# MicrocontrollerPorts.net
KiCad netlist of a schematic drawn in Altium Designer
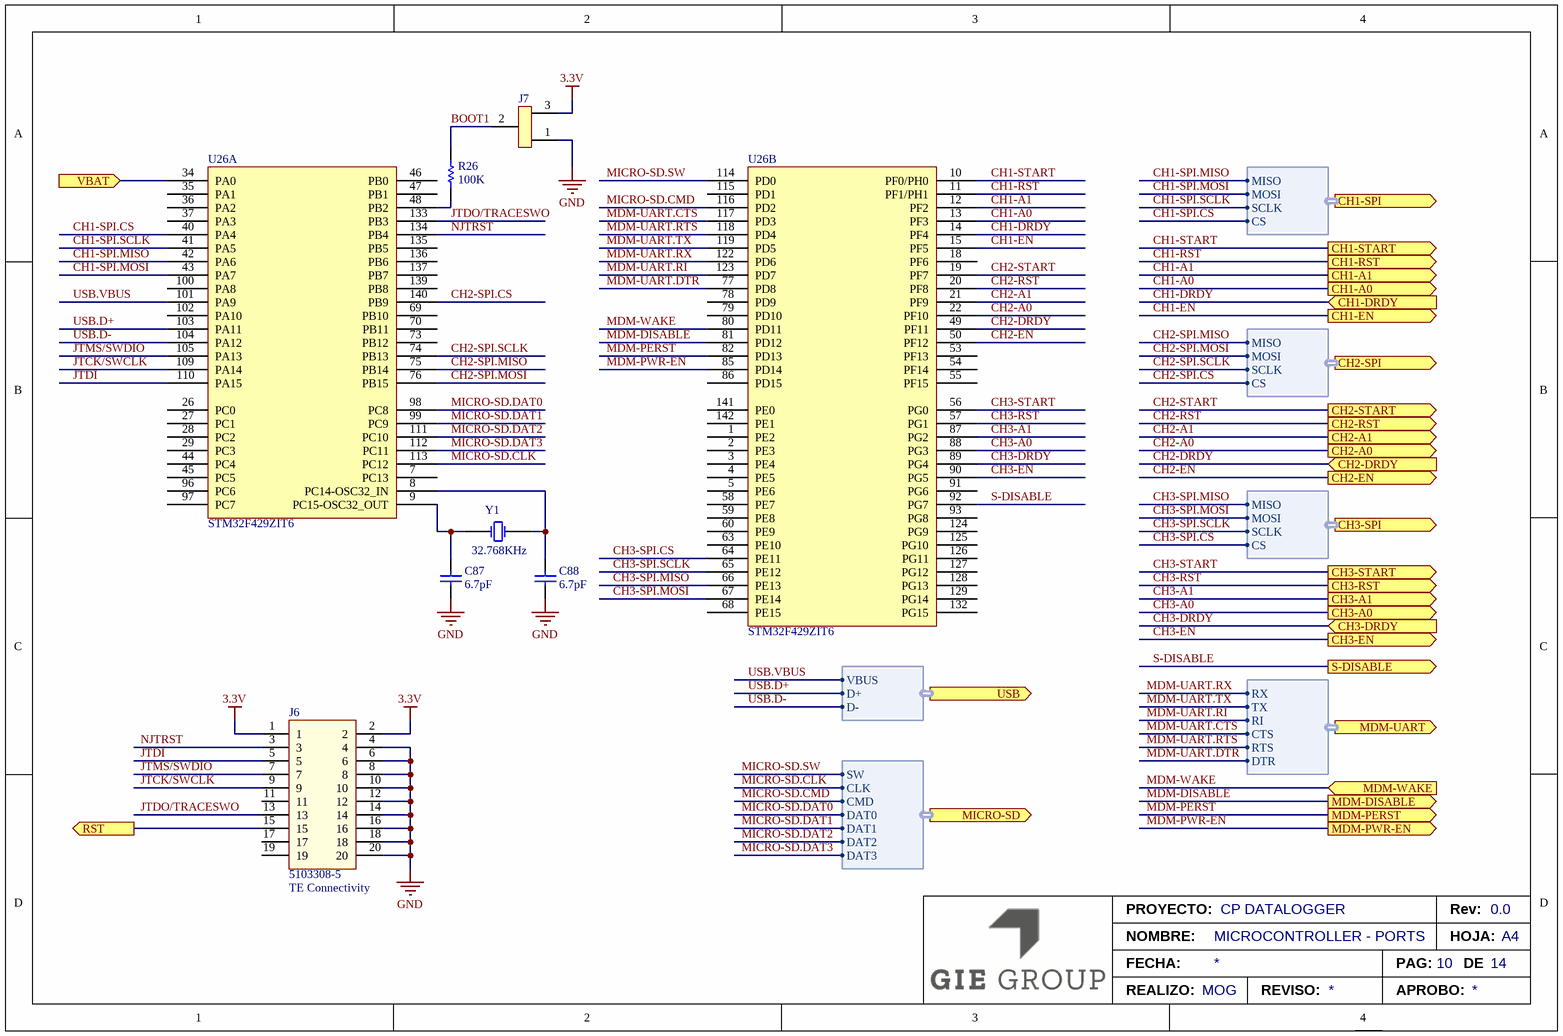
[diagram p0: MicrocontrollerPorts.SchDoc]

(export (version "E")
  (design (tool "Eeschema 10.0.6"))
  (components
    (comp (ref "C87")
      (value "6.7pF")
      (footprint "CAP-0603")
      (description "CAP CER 6.7 pF 50V C0G 0603")
      (fields (field (name "PARTNUMBER") "CBR06C679B5GAC") (field (name "MANUFACTURER") "Kemet"))
      (libsource (lib "Kemet") (part "CBR06C679B5GAC"))
    )
    (comp (ref "C88")
      (value "6.7pF")
      (footprint "CAP-0603")
      (description "CAP CER 6.7 pF 50V C0G 0603")
      (fields (field (name "PARTNUMBER") "CBR06C679B5GAC") (field (name "MANUFACTURER") "Kemet"))
      (libsource (lib "Kemet") (part "CBR06C679B5GAC"))
    )
    (comp (ref "J6")
      (value "5103308-5")
      (footprint "TE-5103308-5")
      (description "CONN HEADER VERT 20POS 2.54MM")
      (fields (field (name "PARTNUMBER") "5103308-5") (field (name "MANUFACTURER") "TE Connectivity"))
      (libsource (lib "TeConnectivity") (part "5103308-5"))
    )
    (comp (ref "J7")
      (value "PRPC003SAAN-RC")
      (footprint "PIN3")
      (description "CONN HEADER .100\" SNGL STR 3POS")
      (fields (field (name "MANUFACTURER") "Sullins Connector Solutions"))
      (libsource (lib "Sullins") (part "PRPC003SAAN-RC"))
    )
    (comp (ref "R26")
      (value "100K")
      (footprint "RES-0603")
      (description "RES SMD 100K OHM 1% 1/10W 0603")
      (fields (field (name "TOLERANCE") "1%") (field (name "MANUFACTURER") "Yageo"))
      (libsource (lib "Yageo") (part "RC0603FR-07100KL"))
    )
    (comp (ref "U26")
      (value "STM32F429ZIT6")
      (footprint "LQFP144")
      (description "IC MCU 32BIT 2MB FLASH 144LQFP")
      (fields (field (name "MANUFACTURER") "STMicroelectronics"))
      (libsource (lib "STMicroelectronics") (part "STM32F429ZIT6"))
    )
    (comp (ref "Y1")
      (value "32.768KHz")
      (footprint "XTAL-ABS07")
      (description "CRYSTAL 32.768KHZ 7PF SMD")
      (fields (field (name "PARTNUMBER") "ABS07-32.768KHZ-7-T") (field (name "MANUFACTURER") "Abracon"))
      (libsource (lib "Abracon") (part "ABS07-32.768KHZ-7-T"))
    )
  )
  (nets
    (net (code "7") (name "/BOOT1") (class "Default")
      (node (ref "J7") (pin "2") (pinfunction "2_2") (pintype "passive"))
      (node (ref "R26") (pin "2") (pinfunction "2_2") (pintype "passive"))
    )
    (net (code "8") (name "/CH1-A0") (class "Default")
      (node (ref "U26") (pin "13") (pinfunction "PF3_13") (pintype "passive"))
    )
    (net (code "9") (name "/CH1-A1") (class "Default")
      (node (ref "U26") (pin "12") (pinfunction "PF2_12") (pintype "passive"))
    )
    (net (code "10") (name "/CH1-DRDY") (class "Default")
      (node (ref "U26") (pin "14") (pinfunction "PF4_14") (pintype "passive"))
    )
    (net (code "11") (name "/CH1-EN") (class "Default")
      (node (ref "U26") (pin "15") (pinfunction "PF5_15") (pintype "passive"))
    )
    (net (code "12") (name "/CH1-RST") (class "Default")
      (node (ref "U26") (pin "11") (pinfunction "PF1/PH1_11") (pintype "passive"))
    )
    (net (code "13") (name "/CH1-SPI.CS") (class "Default")
      (node (ref "U26") (pin "40") (pinfunction "PA4_40") (pintype "passive"))
    )
    (net (code "14") (name "/CH1-SPI.MISO") (class "Default")
      (node (ref "U26") (pin "42") (pinfunction "PA6_42") (pintype "passive"))
    )
    (net (code "15") (name "/CH1-SPI.MOSI") (class "Default")
      (node (ref "U26") (pin "43") (pinfunction "PA7_43") (pintype "passive"))
    )
    (net (code "16") (name "/CH1-SPI.SCLK") (class "Default")
      (node (ref "U26") (pin "41") (pinfunction "PA5_41") (pintype "passive"))
    )
    (net (code "17") (name "/CH1-START") (class "Default")
      (node (ref "U26") (pin "10") (pinfunction "PF0/PH0_10") (pintype "passive"))
    )
    (net (code "18") (name "/CH2-A0") (class "Default")
      (node (ref "U26") (pin "22") (pinfunction "PF10_22") (pintype "passive"))
    )
    (net (code "19") (name "/CH2-A1") (class "Default")
      (node (ref "U26") (pin "21") (pinfunction "PF9_21") (pintype "passive"))
    )
    (net (code "20") (name "/CH2-DRDY") (class "Default")
      (node (ref "U26") (pin "49") (pinfunction "PF11_49") (pintype "passive"))
    )
    (net (code "21") (name "/CH2-EN") (class "Default")
      (node (ref "U26") (pin "50") (pinfunction "PF12_50") (pintype "passive"))
    )
    (net (code "22") (name "/CH2-RST") (class "Default")
      (node (ref "U26") (pin "20") (pinfunction "PF8_20") (pintype "passive"))
    )
    (net (code "23") (name "/CH2-SPI.CS") (class "Default")
      (node (ref "U26") (pin "140") (pinfunction "PB9_140") (pintype "passive"))
    )
    (net (code "24") (name "/CH2-SPI.MISO") (class "Default")
      (node (ref "U26") (pin "75") (pinfunction "PB14_75") (pintype "passive"))
    )
    (net (code "25") (name "/CH2-SPI.MOSI") (class "Default")
      (node (ref "U26") (pin "76") (pinfunction "PB15_76") (pintype "passive"))
    )
    (net (code "26") (name "/CH2-SPI.SCLK") (class "Default")
      (node (ref "U26") (pin "74") (pinfunction "PB13_74") (pintype "passive"))
    )
    (net (code "27") (name "/CH2-START") (class "Default")
      (node (ref "U26") (pin "19") (pinfunction "PF7_19") (pintype "passive"))
    )
    (net (code "28") (name "/CH3-A0") (class "Default")
      (node (ref "U26") (pin "88") (pinfunction "PG3_88") (pintype "passive"))
    )
    (net (code "29") (name "/CH3-A1") (class "Default")
      (node (ref "U26") (pin "87") (pinfunction "PG2_87") (pintype "passive"))
    )
    (net (code "30") (name "/CH3-DRDY") (class "Default")
      (node (ref "U26") (pin "89") (pinfunction "PG4_89") (pintype "passive"))
    )
    (net (code "31") (name "/CH3-EN") (class "Default")
      (node (ref "U26") (pin "90") (pinfunction "PG5_90") (pintype "passive"))
    )
    (net (code "32") (name "/CH3-RST") (class "Default")
      (node (ref "U26") (pin "57") (pinfunction "PG1_57") (pintype "passive"))
    )
    (net (code "33") (name "/CH3-SPI.CS") (class "Default")
      (node (ref "U26") (pin "64") (pinfunction "PE11_64") (pintype "passive"))
    )
    (net (code "34") (name "/CH3-SPI.MISO") (class "Default")
      (node (ref "U26") (pin "66") (pinfunction "PE13_66") (pintype "passive"))
    )
    (net (code "35") (name "/CH3-SPI.MOSI") (class "Default")
      (node (ref "U26") (pin "67") (pinfunction "PE14_67") (pintype "passive"))
    )
    (net (code "36") (name "/CH3-SPI.SCLK") (class "Default")
      (node (ref "U26") (pin "65") (pinfunction "PE12_65") (pintype "passive"))
    )
    (net (code "37") (name "/CH3-START") (class "Default")
      (node (ref "U26") (pin "56") (pinfunction "PG0_56") (pintype "passive"))
    )
    (net (code "38") (name "/JTCK{slash}SWCLK") (class "Default")
      (node (ref "J6") (pin "9") (pinfunction "9_9") (pintype "passive"))
      (node (ref "U26") (pin "109") (pinfunction "PA14_109") (pintype "passive"))
    )
    (net (code "39") (name "/JTDI") (class "Default")
      (node (ref "J6") (pin "5") (pinfunction "5_5") (pintype "passive"))
      (node (ref "U26") (pin "110") (pinfunction "PA15_110") (pintype "passive"))
    )
    (net (code "40") (name "/JTDO{slash}TRACESWO") (class "Default")
      (node (ref "J6") (pin "13") (pinfunction "13_13") (pintype "passive"))
      (node (ref "U26") (pin "133") (pinfunction "PB3_133") (pintype "passive"))
    )
    (net (code "41") (name "/JTMS{slash}SWDIO") (class "Default")
      (node (ref "J6") (pin "7") (pinfunction "7_7") (pintype "passive"))
      (node (ref "U26") (pin "105") (pinfunction "PA13_105") (pintype "passive"))
    )
    (net (code "42") (name "/MDM-DISABLE") (class "Default")
      (node (ref "U26") (pin "81") (pinfunction "PD12_81") (pintype "passive"))
    )
    (net (code "43") (name "/MDM-PERST") (class "Default")
      (node (ref "U26") (pin "82") (pinfunction "PD13_82") (pintype "passive"))
    )
    (net (code "44") (name "/MDM-PWR-EN") (class "Default")
      (node (ref "U26") (pin "85") (pinfunction "PD14_85") (pintype "passive"))
    )
    (net (code "45") (name "/MDM-UART.CTS") (class "Default")
      (node (ref "U26") (pin "117") (pinfunction "PD3_117") (pintype "passive"))
    )
    (net (code "46") (name "/MDM-UART.DTR") (class "Default")
      (node (ref "U26") (pin "77") (pinfunction "PD8_77") (pintype "passive"))
    )
    (net (code "47") (name "/MDM-UART.RI") (class "Default")
      (node (ref "U26") (pin "123") (pinfunction "PD7_123") (pintype "passive"))
    )
    (net (code "48") (name "/MDM-UART.RTS") (class "Default")
      (node (ref "U26") (pin "118") (pinfunction "PD4_118") (pintype "passive"))
    )
    (net (code "49") (name "/MDM-UART.RX") (class "Default")
      (node (ref "U26") (pin "122") (pinfunction "PD6_122") (pintype "passive"))
    )
    (net (code "50") (name "/MDM-UART.TX") (class "Default")
      (node (ref "U26") (pin "119") (pinfunction "PD5_119") (pintype "passive"))
    )
    (net (code "51") (name "/MDM-WAKE") (class "Default")
      (node (ref "U26") (pin "80") (pinfunction "PD11_80") (pintype "passive"))
    )
    (net (code "52") (name "/MICRO-SD.CLK") (class "Default")
      (node (ref "U26") (pin "113") (pinfunction "PC12_113") (pintype "passive"))
    )
    (net (code "53") (name "/MICRO-SD.CMD") (class "Default")
      (node (ref "U26") (pin "116") (pinfunction "PD2_116") (pintype "passive"))
    )
    (net (code "54") (name "/MICRO-SD.DAT0") (class "Default")
      (node (ref "U26") (pin "98") (pinfunction "PC8_98") (pintype "passive"))
    )
    (net (code "55") (name "/MICRO-SD.DAT1") (class "Default")
      (node (ref "U26") (pin "99") (pinfunction "PC9_99") (pintype "passive"))
    )
    (net (code "56") (name "/MICRO-SD.DAT2") (class "Default")
      (node (ref "U26") (pin "111") (pinfunction "PC10_111") (pintype "passive"))
    )
    (net (code "57") (name "/MICRO-SD.DAT3") (class "Default")
      (node (ref "U26") (pin "112") (pinfunction "PC11_112") (pintype "passive"))
    )
    (net (code "58") (name "/MICRO-SD.SW") (class "Default")
      (node (ref "U26") (pin "114") (pinfunction "PD0_114") (pintype "passive"))
    )
    (net (code "59") (name "/NJTRST") (class "Default")
      (node (ref "J6") (pin "3") (pinfunction "3_3") (pintype "passive"))
      (node (ref "U26") (pin "134") (pinfunction "PB4_134") (pintype "passive"))
    )
    (net (code "60") (name "/RST") (class "Default")
      (node (ref "J6") (pin "15") (pinfunction "15_15") (pintype "passive"))
    )
    (net (code "61") (name "/S-DISABLE") (class "Default")
      (node (ref "U26") (pin "92") (pinfunction "PG7_92") (pintype "passive"))
    )
    (net (code "62") (name "/USB.D+") (class "Default")
      (node (ref "U26") (pin "103") (pinfunction "PA11_103") (pintype "passive"))
    )
    (net (code "63") (name "/USB.D-") (class "Default")
      (node (ref "U26") (pin "104") (pinfunction "PA12_104") (pintype "passive"))
    )
    (net (code "64") (name "/USB.VBUS") (class "Default")
      (node (ref "U26") (pin "101") (pinfunction "PA9_101") (pintype "passive"))
    )
    (net (code "65") (name "/VBAT") (class "Default")
      (node (ref "U26") (pin "34") (pinfunction "PA0_34") (pintype "passive"))
    )
    (net (code "72") (name "3.3V") (class "Default")
      (node (ref "J6") (pin "1") (pinfunction "1_1") (pintype "passive"))
      (node (ref "J6") (pin "2") (pinfunction "2_2") (pintype "passive"))
      (node (ref "J7") (pin "3") (pinfunction "3_3") (pintype "passive"))
    )
    (net (code "73") (name "GND") (class "Default")
      (node (ref "C87") (pin "1") (pinfunction "1_1") (pintype "passive"))
      (node (ref "C88") (pin "1") (pinfunction "1_1") (pintype "passive"))
      (node (ref "J6") (pin "10") (pinfunction "10_10") (pintype "passive"))
      (node (ref "J6") (pin "12") (pinfunction "12_12") (pintype "passive"))
      (node (ref "J6") (pin "14") (pinfunction "14_14") (pintype "passive"))
      (node (ref "J6") (pin "16") (pinfunction "16_16") (pintype "passive"))
      (node (ref "J6") (pin "18") (pinfunction "18_18") (pintype "passive"))
      (node (ref "J6") (pin "20") (pinfunction "20_20") (pintype "passive"))
      (node (ref "J6") (pin "4") (pinfunction "4_4") (pintype "passive"))
      (node (ref "J6") (pin "6") (pinfunction "6_6") (pintype "passive"))
      (node (ref "J6") (pin "8") (pinfunction "8_8") (pintype "passive"))
      (node (ref "J7") (pin "1") (pinfunction "1_1") (pintype "passive"))
    )
    (net (code "74") (name "Net-(U26A-PB2)") (class "Default")
      (node (ref "R26") (pin "1") (pinfunction "1_1") (pintype "passive"))
      (node (ref "U26") (pin "48") (pinfunction "PB2_48") (pintype "passive"))
    )
    (net (code "75") (name "Net-(U26A-PC14-OSC32_IN)") (class "Default")
      (node (ref "C88") (pin "2") (pinfunction "2_2") (pintype "passive"))
      (node (ref "U26") (pin "8") (pinfunction "PC14-OSC32_IN_8") (pintype "passive"))
      (node (ref "Y1") (pin "1") (pinfunction "OSC1_1") (pintype "passive"))
    )
    (net (code "76") (name "Net-(U26A-PC15-OSC32_OUT)") (class "Default")
      (node (ref "C87") (pin "2") (pinfunction "2_2") (pintype "passive"))
      (node (ref "U26") (pin "9") (pinfunction "PC15-OSC32_OUT_9") (pintype "passive"))
      (node (ref "Y1") (pin "2") (pinfunction "OSC2_2") (pintype "passive"))
    )
    (net (code "77") (name "unconnected-(J6-Pad11)") (class "Default")
      (node (ref "J6") (pin "11") (pinfunction "11_11") (pintype "passive"))
    )
    (net (code "78") (name "unconnected-(J6-Pad17)") (class "Default")
      (node (ref "J6") (pin "17") (pinfunction "17_17") (pintype "passive"))
    )
    (net (code "79") (name "unconnected-(J6-Pad19)") (class "Default")
      (node (ref "J6") (pin "19") (pinfunction "19_19") (pintype "passive"))
    )
    (net (code "80") (name "unconnected-(U26A-PA1-Pad35)") (class "Default")
      (node (ref "U26") (pin "35") (pinfunction "PA1_35") (pintype "passive"))
    )
    (net (code "81") (name "unconnected-(U26A-PA2-Pad36)") (class "Default")
      (node (ref "U26") (pin "36") (pinfunction "PA2_36") (pintype "passive"))
    )
    (net (code "82") (name "unconnected-(U26A-PA3-Pad37)") (class "Default")
      (node (ref "U26") (pin "37") (pinfunction "PA3_37") (pintype "passive"))
    )
    (net (code "83") (name "unconnected-(U26A-PA8-Pad100)") (class "Default")
      (node (ref "U26") (pin "100") (pinfunction "PA8_100") (pintype "passive"))
    )
    (net (code "84") (name "unconnected-(U26A-PA10-Pad102)") (class "Default")
      (node (ref "U26") (pin "102") (pinfunction "PA10_102") (pintype "passive"))
    )
    (net (code "85") (name "unconnected-(U26A-PB0-Pad46)") (class "Default")
      (node (ref "U26") (pin "46") (pinfunction "PB0_46") (pintype "passive"))
    )
    (net (code "86") (name "unconnected-(U26A-PB1-Pad47)") (class "Default")
      (node (ref "U26") (pin "47") (pinfunction "PB1_47") (pintype "passive"))
    )
    (net (code "87") (name "unconnected-(U26A-PB5-Pad135)") (class "Default")
      (node (ref "U26") (pin "135") (pinfunction "PB5_135") (pintype "passive"))
    )
    (net (code "88") (name "unconnected-(U26A-PB6-Pad136)") (class "Default")
      (node (ref "U26") (pin "136") (pinfunction "PB6_136") (pintype "passive"))
    )
    (net (code "89") (name "unconnected-(U26A-PB7-Pad137)") (class "Default")
      (node (ref "U26") (pin "137") (pinfunction "PB7_137") (pintype "passive"))
    )
    (net (code "90") (name "unconnected-(U26A-PB8-Pad139)") (class "Default")
      (node (ref "U26") (pin "139") (pinfunction "PB8_139") (pintype "passive"))
    )
    (net (code "91") (name "unconnected-(U26A-PB10-Pad69)") (class "Default")
      (node (ref "U26") (pin "69") (pinfunction "PB10_69") (pintype "passive"))
    )
    (net (code "92") (name "unconnected-(U26A-PB11-Pad70)") (class "Default")
      (node (ref "U26") (pin "70") (pinfunction "PB11_70") (pintype "passive"))
    )
    (net (code "93") (name "unconnected-(U26A-PB12-Pad73)") (class "Default")
      (node (ref "U26") (pin "73") (pinfunction "PB12_73") (pintype "passive"))
    )
    (net (code "94") (name "unconnected-(U26A-PC0-Pad26)") (class "Default")
      (node (ref "U26") (pin "26") (pinfunction "PC0_26") (pintype "passive"))
    )
    (net (code "95") (name "unconnected-(U26A-PC1-Pad27)") (class "Default")
      (node (ref "U26") (pin "27") (pinfunction "PC1_27") (pintype "passive"))
    )
    (net (code "96") (name "unconnected-(U26A-PC2-Pad28)") (class "Default")
      (node (ref "U26") (pin "28") (pinfunction "PC2_28") (pintype "passive"))
    )
    (net (code "97") (name "unconnected-(U26A-PC3-Pad29)") (class "Default")
      (node (ref "U26") (pin "29") (pinfunction "PC3_29") (pintype "passive"))
    )
    (net (code "98") (name "unconnected-(U26A-PC4-Pad44)") (class "Default")
      (node (ref "U26") (pin "44") (pinfunction "PC4_44") (pintype "passive"))
    )
    (net (code "99") (name "unconnected-(U26A-PC5-Pad45)") (class "Default")
      (node (ref "U26") (pin "45") (pinfunction "PC5_45") (pintype "passive"))
    )
    (net (code "100") (name "unconnected-(U26A-PC6-Pad96)") (class "Default")
      (node (ref "U26") (pin "96") (pinfunction "PC6_96") (pintype "passive"))
    )
    (net (code "101") (name "unconnected-(U26A-PC7-Pad97)") (class "Default")
      (node (ref "U26") (pin "97") (pinfunction "PC7_97") (pintype "passive"))
    )
    (net (code "102") (name "unconnected-(U26A-PC13-Pad7)") (class "Default")
      (node (ref "U26") (pin "7") (pinfunction "PC13_7") (pintype "passive"))
    )
    (net (code "103") (name "unconnected-(U26B-PD1-Pad115)") (class "Default")
      (node (ref "U26") (pin "115") (pinfunction "PD1_115") (pintype "passive"))
    )
    (net (code "104") (name "unconnected-(U26B-PD9-Pad78)") (class "Default")
      (node (ref "U26") (pin "78") (pinfunction "PD9_78") (pintype "passive"))
    )
    (net (code "105") (name "unconnected-(U26B-PD10-Pad79)") (class "Default")
      (node (ref "U26") (pin "79") (pinfunction "PD10_79") (pintype "passive"))
    )
    (net (code "106") (name "unconnected-(U26B-PD15-Pad86)") (class "Default")
      (node (ref "U26") (pin "86") (pinfunction "PD15_86") (pintype "passive"))
    )
    (net (code "107") (name "unconnected-(U26B-PE0-Pad141)") (class "Default")
      (node (ref "U26") (pin "141") (pinfunction "PE0_141") (pintype "passive"))
    )
    (net (code "108") (name "unconnected-(U26B-PE1-Pad142)") (class "Default")
      (node (ref "U26") (pin "142") (pinfunction "PE1_142") (pintype "passive"))
    )
    (net (code "109") (name "unconnected-(U26B-PE2-Pad1)") (class "Default")
      (node (ref "U26") (pin "1") (pinfunction "PE2_1") (pintype "passive"))
    )
    (net (code "110") (name "unconnected-(U26B-PE3-Pad2)") (class "Default")
      (node (ref "U26") (pin "2") (pinfunction "PE3_2") (pintype "passive"))
    )
    (net (code "111") (name "unconnected-(U26B-PE4-Pad3)") (class "Default")
      (node (ref "U26") (pin "3") (pinfunction "PE4_3") (pintype "passive"))
    )
    (net (code "112") (name "unconnected-(U26B-PE5-Pad4)") (class "Default")
      (node (ref "U26") (pin "4") (pinfunction "PE5_4") (pintype "passive"))
    )
    (net (code "113") (name "unconnected-(U26B-PE6-Pad5)") (class "Default")
      (node (ref "U26") (pin "5") (pinfunction "PE6_5") (pintype "passive"))
    )
    (net (code "114") (name "unconnected-(U26B-PE7-Pad58)") (class "Default")
      (node (ref "U26") (pin "58") (pinfunction "PE7_58") (pintype "passive"))
    )
    (net (code "115") (name "unconnected-(U26B-PE8-Pad59)") (class "Default")
      (node (ref "U26") (pin "59") (pinfunction "PE8_59") (pintype "passive"))
    )
    (net (code "116") (name "unconnected-(U26B-PE9-Pad60)") (class "Default")
      (node (ref "U26") (pin "60") (pinfunction "PE9_60") (pintype "passive"))
    )
    (net (code "117") (name "unconnected-(U26B-PE10-Pad63)") (class "Default")
      (node (ref "U26") (pin "63") (pinfunction "PE10_63") (pintype "passive"))
    )
    (net (code "118") (name "unconnected-(U26B-PE15-Pad68)") (class "Default")
      (node (ref "U26") (pin "68") (pinfunction "PE15_68") (pintype "passive"))
    )
    (net (code "119") (name "unconnected-(U26B-PF6-Pad18)") (class "Default")
      (node (ref "U26") (pin "18") (pinfunction "PF6_18") (pintype "passive"))
    )
    (net (code "120") (name "unconnected-(U26B-PF13-Pad53)") (class "Default")
      (node (ref "U26") (pin "53") (pinfunction "PF13_53") (pintype "passive"))
    )
    (net (code "121") (name "unconnected-(U26B-PF14-Pad54)") (class "Default")
      (node (ref "U26") (pin "54") (pinfunction "PF14_54") (pintype "passive"))
    )
    (net (code "122") (name "unconnected-(U26B-PF15-Pad55)") (class "Default")
      (node (ref "U26") (pin "55") (pinfunction "PF15_55") (pintype "passive"))
    )
    (net (code "123") (name "unconnected-(U26B-PG6-Pad91)") (class "Default")
      (node (ref "U26") (pin "91") (pinfunction "PG6_91") (pintype "passive"))
    )
    (net (code "124") (name "unconnected-(U26B-PG8-Pad93)") (class "Default")
      (node (ref "U26") (pin "93") (pinfunction "PG8_93") (pintype "passive"))
    )
    (net (code "125") (name "unconnected-(U26B-PG9-Pad124)") (class "Default")
      (node (ref "U26") (pin "124") (pinfunction "PG9_124") (pintype "passive"))
    )
    (net (code "126") (name "unconnected-(U26B-PG10-Pad125)") (class "Default")
      (node (ref "U26") (pin "125") (pinfunction "PG10_125") (pintype "passive"))
    )
    (net (code "127") (name "unconnected-(U26B-PG11-Pad126)") (class "Default")
      (node (ref "U26") (pin "126") (pinfunction "PG11_126") (pintype "passive"))
    )
    (net (code "128") (name "unconnected-(U26B-PG12-Pad127)") (class "Default")
      (node (ref "U26") (pin "127") (pinfunction "PG12_127") (pintype "passive"))
    )
    (net (code "129") (name "unconnected-(U26B-PG13-Pad128)") (class "Default")
      (node (ref "U26") (pin "128") (pinfunction "PG13_128") (pintype "passive"))
    )
    (net (code "130") (name "unconnected-(U26B-PG14-Pad129)") (class "Default")
      (node (ref "U26") (pin "129") (pinfunction "PG14_129") (pintype "passive"))
    )
    (net (code "131") (name "unconnected-(U26B-PG15-Pad132)") (class "Default")
      (node (ref "U26") (pin "132") (pinfunction "PG15_132") (pintype "passive"))
    )
  )
)
